# Quadflat-customized.net
KiCad netlist of a schematic drawn in EAGLE
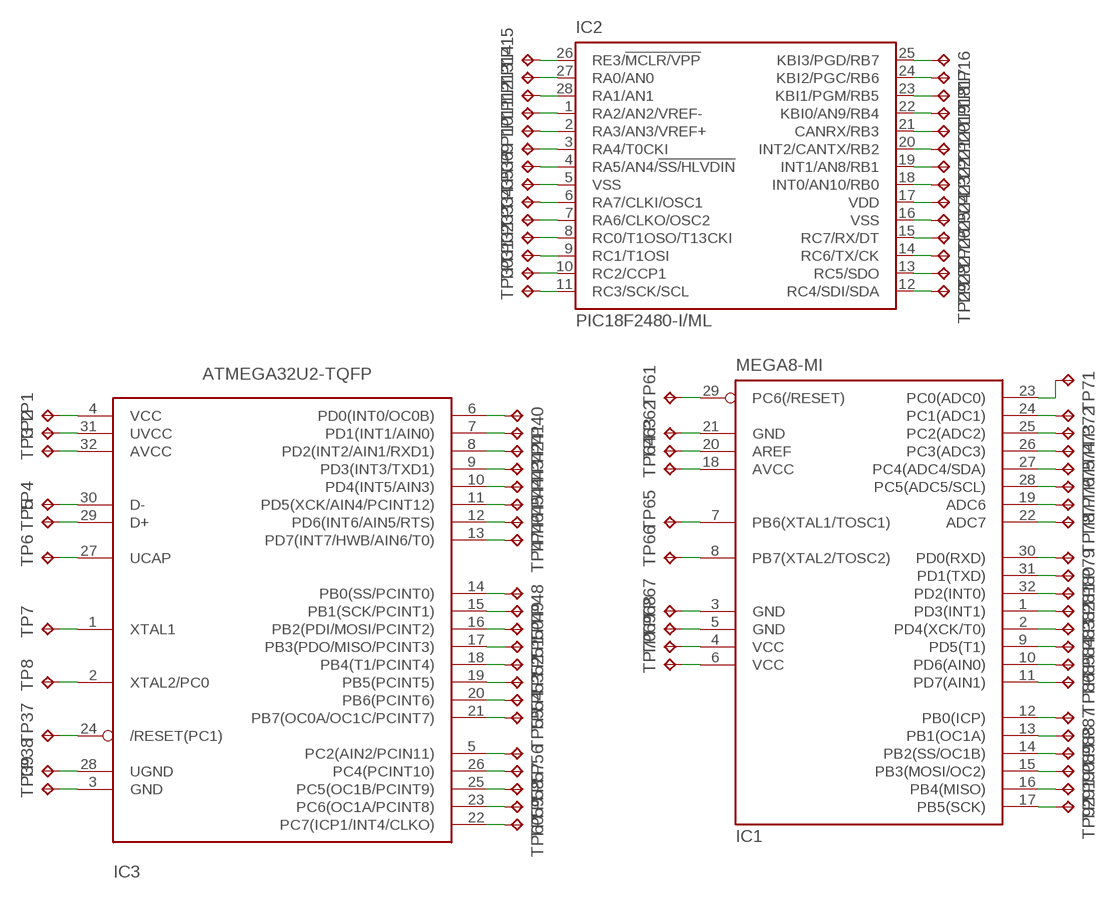
[diagram p0: schematic, sheet 2]

(export (version "E")
  (design (tool "Eeschema 10.0.6"))
  (components
    (comp (ref "IC1")
      (value "MEGA8-MI")
      (footprint "eagle-import:MLF32")
      (fields (field (name "MPN") "ATMEGA88PA-MU"))
      (libsource (lib "eagle-import") (part "MEGA8-MI"))
    )
    (comp (ref "IC2")
      (value "PIC18F2480-I/ML")
      (footprint "eagle-import:QFN28-ML_6X6MM")
      (fields (field (name "MF") "MICROCHIP"))
      (libsource (lib "eagle-import") (part "PIC18F280-I/ML4"))
    )
    (comp (ref "IC3")
      (value "ATMEGA32U2-TQFP")
      (footprint "eagle-import:TQFP32-08")
      (libsource (lib "eagle-import") (part "ATMEGA32U2-TQFP"))
    )
    (comp (ref "TP1")
      (value "TPPAD1-13Y")
      (footprint "eagle-import:P1-13Y")
      (libsource (lib "eagle-import") (part "TPPAD1-13Y"))
    )
    (comp (ref "TP2")
      (value "TPPAD1-13Y")
      (footprint "eagle-import:P1-13Y")
      (libsource (lib "eagle-import") (part "TPPAD1-13Y"))
    )
    (comp (ref "TP3")
      (value "TPPAD1-13Y")
      (footprint "eagle-import:P1-13Y")
      (libsource (lib "eagle-import") (part "TPPAD1-13Y"))
    )
    (comp (ref "TP4")
      (value "TPPAD1-13Y")
      (footprint "eagle-import:P1-13Y")
      (libsource (lib "eagle-import") (part "TPPAD1-13Y"))
    )
    (comp (ref "TP5")
      (value "TPPAD1-13Y")
      (footprint "eagle-import:P1-13Y")
      (libsource (lib "eagle-import") (part "TPPAD1-13Y"))
    )
    (comp (ref "TP6")
      (value "TPPAD1-13Y")
      (footprint "eagle-import:P1-13Y")
      (libsource (lib "eagle-import") (part "TPPAD1-13Y"))
    )
    (comp (ref "TP7")
      (value "TPPAD1-13Y")
      (footprint "eagle-import:P1-13Y")
      (libsource (lib "eagle-import") (part "TPPAD1-13Y"))
    )
    (comp (ref "TP8")
      (value "TPPAD1-13Y")
      (footprint "eagle-import:P1-13Y")
      (libsource (lib "eagle-import") (part "TPPAD1-13Y"))
    )
    (comp (ref "TP9")
      (value "TPPAD1-13Y")
      (footprint "eagle-import:P1-13Y")
      (libsource (lib "eagle-import") (part "TPPAD1-13Y"))
    )
    (comp (ref "TP10")
      (value "TPPAD1-13Y")
      (footprint "eagle-import:P1-13Y")
      (libsource (lib "eagle-import") (part "TPPAD1-13Y"))
    )
    (comp (ref "TP11")
      (value "TPPAD1-13Y")
      (footprint "eagle-import:P1-13Y")
      (libsource (lib "eagle-import") (part "TPPAD1-13Y"))
    )
    (comp (ref "TP12")
      (value "TPPAD1-13Y")
      (footprint "eagle-import:P1-13Y")
      (libsource (lib "eagle-import") (part "TPPAD1-13Y"))
    )
    (comp (ref "TP13")
      (value "TPPAD1-13Y")
      (footprint "eagle-import:P1-13Y")
      (libsource (lib "eagle-import") (part "TPPAD1-13Y"))
    )
    (comp (ref "TP14")
      (value "TPPAD1-13Y")
      (footprint "eagle-import:P1-13Y")
      (libsource (lib "eagle-import") (part "TPPAD1-13Y"))
    )
    (comp (ref "TP15")
      (value "TPPAD1-13Y")
      (footprint "eagle-import:P1-13Y")
      (libsource (lib "eagle-import") (part "TPPAD1-13Y"))
    )
    (comp (ref "TP16")
      (value "TPPAD1-13Y")
      (footprint "eagle-import:P1-13Y")
      (libsource (lib "eagle-import") (part "TPPAD1-13Y"))
    )
    (comp (ref "TP17")
      (value "TPPAD1-13Y")
      (footprint "eagle-import:P1-13Y")
      (libsource (lib "eagle-import") (part "TPPAD1-13Y"))
    )
    (comp (ref "TP18")
      (value "TPPAD1-13Y")
      (footprint "eagle-import:P1-13Y")
      (libsource (lib "eagle-import") (part "TPPAD1-13Y"))
    )
    (comp (ref "TP19")
      (value "TPPAD1-13Y")
      (footprint "eagle-import:P1-13Y")
      (libsource (lib "eagle-import") (part "TPPAD1-13Y"))
    )
    (comp (ref "TP20")
      (value "TPPAD1-13Y")
      (footprint "eagle-import:P1-13Y")
      (libsource (lib "eagle-import") (part "TPPAD1-13Y"))
    )
    (comp (ref "TP21")
      (value "TPPAD1-13Y")
      (footprint "eagle-import:P1-13Y")
      (libsource (lib "eagle-import") (part "TPPAD1-13Y"))
    )
    (comp (ref "TP22")
      (value "TPPAD1-13Y")
      (footprint "eagle-import:P1-13Y")
      (libsource (lib "eagle-import") (part "TPPAD1-13Y"))
    )
    (comp (ref "TP23")
      (value "TPPAD1-13Y")
      (footprint "eagle-import:P1-13Y")
      (libsource (lib "eagle-import") (part "TPPAD1-13Y"))
    )
    (comp (ref "TP24")
      (value "TPPAD1-13Y")
      (footprint "eagle-import:P1-13Y")
      (libsource (lib "eagle-import") (part "TPPAD1-13Y"))
    )
    (comp (ref "TP25")
      (value "TPPAD1-13Y")
      (footprint "eagle-import:P1-13Y")
      (libsource (lib "eagle-import") (part "TPPAD1-13Y"))
    )
    (comp (ref "TP26")
      (value "TPPAD1-13Y")
      (footprint "eagle-import:P1-13Y")
      (libsource (lib "eagle-import") (part "TPPAD1-13Y"))
    )
    (comp (ref "TP27")
      (value "TPPAD1-13Y")
      (footprint "eagle-import:P1-13Y")
      (libsource (lib "eagle-import") (part "TPPAD1-13Y"))
    )
    (comp (ref "TP28")
      (value "TPPAD1-13Y")
      (footprint "eagle-import:P1-13Y")
      (libsource (lib "eagle-import") (part "TPPAD1-13Y"))
    )
    (comp (ref "TP29")
      (value "TPPAD1-13Y")
      (footprint "eagle-import:P1-13Y")
      (libsource (lib "eagle-import") (part "TPPAD1-13Y"))
    )
    (comp (ref "TP30")
      (value "TPPAD1-13Y")
      (footprint "eagle-import:P1-13Y")
      (libsource (lib "eagle-import") (part "TPPAD1-13Y"))
    )
    (comp (ref "TP31")
      (value "TPPAD1-13Y")
      (footprint "eagle-import:P1-13Y")
      (libsource (lib "eagle-import") (part "TPPAD1-13Y"))
    )
    (comp (ref "TP32")
      (value "TPPAD1-13Y")
      (footprint "eagle-import:P1-13Y")
      (libsource (lib "eagle-import") (part "TPPAD1-13Y"))
    )
    (comp (ref "TP33")
      (value "TPPAD1-13Y")
      (footprint "eagle-import:P1-13Y")
      (libsource (lib "eagle-import") (part "TPPAD1-13Y"))
    )
    (comp (ref "TP34")
      (value "TPPAD1-13Y")
      (footprint "eagle-import:P1-13Y")
      (libsource (lib "eagle-import") (part "TPPAD1-13Y"))
    )
    (comp (ref "TP35")
      (value "TPPAD1-13Y")
      (footprint "eagle-import:P1-13Y")
      (libsource (lib "eagle-import") (part "TPPAD1-13Y"))
    )
    (comp (ref "TP36")
      (value "TPPAD1-13Y")
      (footprint "eagle-import:P1-13Y")
      (libsource (lib "eagle-import") (part "TPPAD1-13Y"))
    )
    (comp (ref "TP37")
      (value "TPPAD1-13Y")
      (footprint "eagle-import:P1-13Y")
      (libsource (lib "eagle-import") (part "TPPAD1-13Y"))
    )
    (comp (ref "TP38")
      (value "TPPAD1-13Y")
      (footprint "eagle-import:P1-13Y")
      (libsource (lib "eagle-import") (part "TPPAD1-13Y"))
    )
    (comp (ref "TP39")
      (value "TPPAD1-13Y")
      (footprint "eagle-import:P1-13Y")
      (libsource (lib "eagle-import") (part "TPPAD1-13Y"))
    )
    (comp (ref "TP40")
      (value "TPPAD1-13Y")
      (footprint "eagle-import:P1-13Y")
      (libsource (lib "eagle-import") (part "TPPAD1-13Y"))
    )
    (comp (ref "TP41")
      (value "TPPAD1-13Y")
      (footprint "eagle-import:P1-13Y")
      (libsource (lib "eagle-import") (part "TPPAD1-13Y"))
    )
    (comp (ref "TP42")
      (value "TPPAD1-13Y")
      (footprint "eagle-import:P1-13Y")
      (libsource (lib "eagle-import") (part "TPPAD1-13Y"))
    )
    (comp (ref "TP43")
      (value "TPPAD1-13Y")
      (footprint "eagle-import:P1-13Y")
      (libsource (lib "eagle-import") (part "TPPAD1-13Y"))
    )
    (comp (ref "TP44")
      (value "TPPAD1-13Y")
      (footprint "eagle-import:P1-13Y")
      (libsource (lib "eagle-import") (part "TPPAD1-13Y"))
    )
    (comp (ref "TP45")
      (value "TPPAD1-13Y")
      (footprint "eagle-import:P1-13Y")
      (libsource (lib "eagle-import") (part "TPPAD1-13Y"))
    )
    (comp (ref "TP46")
      (value "TPPAD1-13Y")
      (footprint "eagle-import:P1-13Y")
      (libsource (lib "eagle-import") (part "TPPAD1-13Y"))
    )
    (comp (ref "TP47")
      (value "TPPAD1-13Y")
      (footprint "eagle-import:P1-13Y")
      (libsource (lib "eagle-import") (part "TPPAD1-13Y"))
    )
    (comp (ref "TP48")
      (value "TPPAD1-13Y")
      (footprint "eagle-import:P1-13Y")
      (libsource (lib "eagle-import") (part "TPPAD1-13Y"))
    )
    (comp (ref "TP49")
      (value "TPPAD1-13Y")
      (footprint "eagle-import:P1-13Y")
      (libsource (lib "eagle-import") (part "TPPAD1-13Y"))
    )
    (comp (ref "TP50")
      (value "TPPAD1-13Y")
      (footprint "eagle-import:P1-13Y")
      (libsource (lib "eagle-import") (part "TPPAD1-13Y"))
    )
    (comp (ref "TP51")
      (value "TPPAD1-13Y")
      (footprint "eagle-import:P1-13Y")
      (libsource (lib "eagle-import") (part "TPPAD1-13Y"))
    )
    (comp (ref "TP52")
      (value "TPPAD1-13Y")
      (footprint "eagle-import:P1-13Y")
      (libsource (lib "eagle-import") (part "TPPAD1-13Y"))
    )
    (comp (ref "TP53")
      (value "TPPAD1-13Y")
      (footprint "eagle-import:P1-13Y")
      (libsource (lib "eagle-import") (part "TPPAD1-13Y"))
    )
    (comp (ref "TP54")
      (value "TPPAD1-13Y")
      (footprint "eagle-import:P1-13Y")
      (libsource (lib "eagle-import") (part "TPPAD1-13Y"))
    )
    (comp (ref "TP55")
      (value "TPPAD1-13Y")
      (footprint "eagle-import:P1-13Y")
      (libsource (lib "eagle-import") (part "TPPAD1-13Y"))
    )
    (comp (ref "TP56")
      (value "TPPAD1-13Y")
      (footprint "eagle-import:P1-13Y")
      (libsource (lib "eagle-import") (part "TPPAD1-13Y"))
    )
    (comp (ref "TP57")
      (value "TPPAD1-13Y")
      (footprint "eagle-import:P1-13Y")
      (libsource (lib "eagle-import") (part "TPPAD1-13Y"))
    )
    (comp (ref "TP58")
      (value "TPPAD1-13Y")
      (footprint "eagle-import:P1-13Y")
      (libsource (lib "eagle-import") (part "TPPAD1-13Y"))
    )
    (comp (ref "TP59")
      (value "TPPAD1-13Y")
      (footprint "eagle-import:P1-13Y")
      (libsource (lib "eagle-import") (part "TPPAD1-13Y"))
    )
    (comp (ref "TP60")
      (value "TPPAD1-13Y")
      (footprint "eagle-import:P1-13Y")
      (libsource (lib "eagle-import") (part "TPPAD1-13Y"))
    )
    (comp (ref "TP61")
      (value "TPPAD1-13Y")
      (footprint "eagle-import:P1-13Y")
      (libsource (lib "eagle-import") (part "TPPAD1-13Y"))
    )
    (comp (ref "TP62")
      (value "TPPAD1-13Y")
      (footprint "eagle-import:P1-13Y")
      (libsource (lib "eagle-import") (part "TPPAD1-13Y"))
    )
    (comp (ref "TP63")
      (value "TPPAD1-13Y")
      (footprint "eagle-import:P1-13Y")
      (libsource (lib "eagle-import") (part "TPPAD1-13Y"))
    )
    (comp (ref "TP64")
      (value "TPPAD1-13Y")
      (footprint "eagle-import:P1-13Y")
      (libsource (lib "eagle-import") (part "TPPAD1-13Y"))
    )
    (comp (ref "TP65")
      (value "TPPAD1-13Y")
      (footprint "eagle-import:P1-13Y")
      (libsource (lib "eagle-import") (part "TPPAD1-13Y"))
    )
    (comp (ref "TP66")
      (value "TPPAD1-13Y")
      (footprint "eagle-import:P1-13Y")
      (libsource (lib "eagle-import") (part "TPPAD1-13Y"))
    )
    (comp (ref "TP67")
      (value "TPPAD1-13Y")
      (footprint "eagle-import:P1-13Y")
      (libsource (lib "eagle-import") (part "TPPAD1-13Y"))
    )
    (comp (ref "TP68")
      (value "TPPAD1-13Y")
      (footprint "eagle-import:P1-13Y")
      (libsource (lib "eagle-import") (part "TPPAD1-13Y"))
    )
    (comp (ref "TP69")
      (value "TPPAD1-13Y")
      (footprint "eagle-import:P1-13Y")
      (libsource (lib "eagle-import") (part "TPPAD1-13Y"))
    )
    (comp (ref "TP70")
      (value "TPPAD1-13Y")
      (footprint "eagle-import:P1-13Y")
      (libsource (lib "eagle-import") (part "TPPAD1-13Y"))
    )
    (comp (ref "TP71")
      (value "TPPAD1-13Y")
      (footprint "eagle-import:P1-13Y")
      (libsource (lib "eagle-import") (part "TPPAD1-13Y"))
    )
    (comp (ref "TP72")
      (value "TPPAD1-13Y")
      (footprint "eagle-import:P1-13Y")
      (libsource (lib "eagle-import") (part "TPPAD1-13Y"))
    )
    (comp (ref "TP73")
      (value "TPPAD1-13Y")
      (footprint "eagle-import:P1-13Y")
      (libsource (lib "eagle-import") (part "TPPAD1-13Y"))
    )
    (comp (ref "TP74")
      (value "TPPAD1-13Y")
      (footprint "eagle-import:P1-13Y")
      (libsource (lib "eagle-import") (part "TPPAD1-13Y"))
    )
    (comp (ref "TP75")
      (value "TPPAD1-13Y")
      (footprint "eagle-import:P1-13Y")
      (libsource (lib "eagle-import") (part "TPPAD1-13Y"))
    )
    (comp (ref "TP76")
      (value "TPPAD1-13Y")
      (footprint "eagle-import:P1-13Y")
      (libsource (lib "eagle-import") (part "TPPAD1-13Y"))
    )
    (comp (ref "TP77")
      (value "TPPAD1-13Y")
      (footprint "eagle-import:P1-13Y")
      (libsource (lib "eagle-import") (part "TPPAD1-13Y"))
    )
    (comp (ref "TP78")
      (value "TPPAD1-13Y")
      (footprint "eagle-import:P1-13Y")
      (libsource (lib "eagle-import") (part "TPPAD1-13Y"))
    )
    (comp (ref "TP79")
      (value "TPPAD1-13Y")
      (footprint "eagle-import:P1-13Y")
      (libsource (lib "eagle-import") (part "TPPAD1-13Y"))
    )
    (comp (ref "TP80")
      (value "TPPAD1-13Y")
      (footprint "eagle-import:P1-13Y")
      (libsource (lib "eagle-import") (part "TPPAD1-13Y"))
    )
    (comp (ref "TP81")
      (value "TPPAD1-13Y")
      (footprint "eagle-import:P1-13Y")
      (libsource (lib "eagle-import") (part "TPPAD1-13Y"))
    )
    (comp (ref "TP82")
      (value "TPPAD1-13Y")
      (footprint "eagle-import:P1-13Y")
      (libsource (lib "eagle-import") (part "TPPAD1-13Y"))
    )
    (comp (ref "TP83")
      (value "TPPAD1-13Y")
      (footprint "eagle-import:P1-13Y")
      (libsource (lib "eagle-import") (part "TPPAD1-13Y"))
    )
    (comp (ref "TP84")
      (value "TPPAD1-13Y")
      (footprint "eagle-import:P1-13Y")
      (libsource (lib "eagle-import") (part "TPPAD1-13Y"))
    )
    (comp (ref "TP85")
      (value "TPPAD1-13Y")
      (footprint "eagle-import:P1-13Y")
      (libsource (lib "eagle-import") (part "TPPAD1-13Y"))
    )
    (comp (ref "TP86")
      (value "TPPAD1-13Y")
      (footprint "eagle-import:P1-13Y")
      (libsource (lib "eagle-import") (part "TPPAD1-13Y"))
    )
    (comp (ref "TP87")
      (value "TPPAD1-13Y")
      (footprint "eagle-import:P1-13Y")
      (libsource (lib "eagle-import") (part "TPPAD1-13Y"))
    )
    (comp (ref "TP88")
      (value "TPPAD1-13Y")
      (footprint "eagle-import:P1-13Y")
      (libsource (lib "eagle-import") (part "TPPAD1-13Y"))
    )
    (comp (ref "TP89")
      (value "TPPAD1-13Y")
      (footprint "eagle-import:P1-13Y")
      (libsource (lib "eagle-import") (part "TPPAD1-13Y"))
    )
    (comp (ref "TP90")
      (value "TPPAD1-13Y")
      (footprint "eagle-import:P1-13Y")
      (libsource (lib "eagle-import") (part "TPPAD1-13Y"))
    )
    (comp (ref "TP91")
      (value "TPPAD1-13Y")
      (footprint "eagle-import:P1-13Y")
      (libsource (lib "eagle-import") (part "TPPAD1-13Y"))
    )
    (comp (ref "TP92")
      (value "TPPAD1-13Y")
      (footprint "eagle-import:P1-13Y")
      (libsource (lib "eagle-import") (part "TPPAD1-13Y"))
    )
  )
  (nets
    (net (code "1") (name "Net-(IC1-ADC6)") (class "Default")
      (node (ref "IC1") (pin "19") (pinfunction "ADC6_19") (pintype "bidirectional"))
      (node (ref "TP77") (pin "TP") (pinfunction "TP_TP") (pintype "input"))
    )
    (net (code "2") (name "Net-(IC1-ADC7)") (class "Default")
      (node (ref "IC1") (pin "22") (pinfunction "ADC7_22") (pintype "bidirectional"))
      (node (ref "TP78") (pin "TP") (pinfunction "TP_TP") (pintype "input"))
    )
    (net (code "3") (name "Net-(IC1-AREF)") (class "Default")
      (node (ref "IC1") (pin "20") (pinfunction "AREF_20") (pintype "passive"))
      (node (ref "TP63") (pin "TP") (pinfunction "TP_TP") (pintype "input"))
    )
    (net (code "4") (name "Net-(IC1-AVCC)") (class "Default")
      (node (ref "IC1") (pin "18") (pinfunction "AVCC_18") (pintype "power_in"))
      (node (ref "TP64") (pin "TP") (pinfunction "TP_TP") (pintype "input"))
    )
    (net (code "5") (name "Net-(IC1-GND-Pad3)") (class "Default")
      (node (ref "IC1") (pin "3") (pinfunction "GND_3") (pintype "power_in"))
      (node (ref "TP67") (pin "TP") (pinfunction "TP_TP") (pintype "input"))
    )
    (net (code "6") (name "Net-(IC1-GND-Pad5)") (class "Default")
      (node (ref "IC1") (pin "5") (pinfunction "GND_5") (pintype "power_in"))
      (node (ref "TP68") (pin "TP") (pinfunction "TP_TP") (pintype "input"))
    )
    (net (code "7") (name "Net-(IC1-GND-Pad21)") (class "Default")
      (node (ref "IC1") (pin "21") (pinfunction "GND_21") (pintype "power_in"))
      (node (ref "TP62") (pin "TP") (pinfunction "TP_TP") (pintype "input"))
    )
    (net (code "8") (name "Net-(IC1-PB0(ICP))") (class "Default")
      (node (ref "IC1") (pin "12") (pinfunction "PB0(ICP)_12") (pintype "bidirectional"))
      (node (ref "TP87") (pin "TP") (pinfunction "TP_TP") (pintype "input"))
    )
    (net (code "9") (name "Net-(IC1-PB1(OC1A))") (class "Default")
      (node (ref "IC1") (pin "13") (pinfunction "PB1(OC1A)_13") (pintype "bidirectional"))
      (node (ref "TP88") (pin "TP") (pinfunction "TP_TP") (pintype "input"))
    )
    (net (code "10") (name "Net-(IC1-PB2(SS{slash}OC1B))") (class "Default")
      (node (ref "IC1") (pin "14") (pinfunction "PB2(SS/OC1B)_14") (pintype "bidirectional"))
      (node (ref "TP89") (pin "TP") (pinfunction "TP_TP") (pintype "input"))
    )
    (net (code "11") (name "Net-(IC1-PB3(MOSI{slash}OC2))") (class "Default")
      (node (ref "IC1") (pin "15") (pinfunction "PB3(MOSI/OC2)_15") (pintype "bidirectional"))
      (node (ref "TP90") (pin "TP") (pinfunction "TP_TP") (pintype "input"))
    )
    (net (code "12") (name "Net-(IC1-PB4(MISO))") (class "Default")
      (node (ref "IC1") (pin "16") (pinfunction "PB4(MISO)_16") (pintype "bidirectional"))
      (node (ref "TP91") (pin "TP") (pinfunction "TP_TP") (pintype "input"))
    )
    (net (code "13") (name "Net-(IC1-PB5(SCK))") (class "Default")
      (node (ref "IC1") (pin "17") (pinfunction "PB5(SCK)_17") (pintype "bidirectional"))
      (node (ref "TP92") (pin "TP") (pinfunction "TP_TP") (pintype "input"))
    )
    (net (code "14") (name "Net-(IC1-PB6(XTAL1{slash}TOSC1))") (class "Default")
      (node (ref "IC1") (pin "7") (pinfunction "PB6(XTAL1/TOSC1)_7") (pintype "bidirectional"))
      (node (ref "TP65") (pin "TP") (pinfunction "TP_TP") (pintype "input"))
    )
    (net (code "15") (name "Net-(IC1-PB7(XTAL2{slash}TOSC2))") (class "Default")
      (node (ref "IC1") (pin "8") (pinfunction "PB7(XTAL2/TOSC2)_8") (pintype "bidirectional"))
      (node (ref "TP66") (pin "TP") (pinfunction "TP_TP") (pintype "input"))
    )
    (net (code "16") (name "Net-(IC1-PC0(ADC0))") (class "Default")
      (node (ref "IC1") (pin "23") (pinfunction "PC0(ADC0)_23") (pintype "bidirectional"))
      (node (ref "TP71") (pin "TP") (pinfunction "TP_TP") (pintype "input"))
    )
    (net (code "17") (name "Net-(IC1-PC1(ADC1))") (class "Default")
      (node (ref "IC1") (pin "24") (pinfunction "PC1(ADC1)_24") (pintype "bidirectional"))
      (node (ref "TP72") (pin "TP") (pinfunction "TP_TP") (pintype "input"))
    )
    (net (code "18") (name "Net-(IC1-PC2(ADC2))") (class "Default")
      (node (ref "IC1") (pin "25") (pinfunction "PC2(ADC2)_25") (pintype "bidirectional"))
      (node (ref "TP73") (pin "TP") (pinfunction "TP_TP") (pintype "input"))
    )
    (net (code "19") (name "Net-(IC1-PC3(ADC3))") (class "Default")
      (node (ref "IC1") (pin "26") (pinfunction "PC3(ADC3)_26") (pintype "bidirectional"))
      (node (ref "TP74") (pin "TP") (pinfunction "TP_TP") (pintype "input"))
    )
    (net (code "20") (name "Net-(IC1-PC4(ADC4{slash}SDA))") (class "Default")
      (node (ref "IC1") (pin "27") (pinfunction "PC4(ADC4/SDA)_27") (pintype "bidirectional"))
      (node (ref "TP75") (pin "TP") (pinfunction "TP_TP") (pintype "input"))
    )
    (net (code "21") (name "Net-(IC1-PC5(ADC5{slash}SCL))") (class "Default")
      (node (ref "IC1") (pin "28") (pinfunction "PC5(ADC5/SCL)_28") (pintype "bidirectional"))
      (node (ref "TP76") (pin "TP") (pinfunction "TP_TP") (pintype "input"))
    )
    (net (code "22") (name "Net-(IC1-PC6({slash}RESET))") (class "Default")
      (node (ref "IC1") (pin "29") (pinfunction "PC6(/RESET)_29") (pintype "bidirectional"))
      (node (ref "TP61") (pin "TP") (pinfunction "TP_TP") (pintype "input"))
    )
    (net (code "23") (name "Net-(IC1-PD0(RXD))") (class "Default")
      (node (ref "IC1") (pin "30") (pinfunction "PD0(RXD)_30") (pintype "bidirectional"))
      (node (ref "TP79") (pin "TP") (pinfunction "TP_TP") (pintype "input"))
    )
    (net (code "24") (name "Net-(IC1-PD1(TXD))") (class "Default")
      (node (ref "IC1") (pin "31") (pinfunction "PD1(TXD)_31") (pintype "bidirectional"))
      (node (ref "TP80") (pin "TP") (pinfunction "TP_TP") (pintype "input"))
    )
    (net (code "25") (name "Net-(IC1-PD2(INT0))") (class "Default")
      (node (ref "IC1") (pin "32") (pinfunction "PD2(INT0)_32") (pintype "bidirectional"))
      (node (ref "TP81") (pin "TP") (pinfunction "TP_TP") (pintype "input"))
    )
    (net (code "26") (name "Net-(IC1-PD3(INT1))") (class "Default")
      (node (ref "IC1") (pin "1") (pinfunction "PD3(INT1)_1") (pintype "bidirectional"))
      (node (ref "TP82") (pin "TP") (pinfunction "TP_TP") (pintype "input"))
    )
    (net (code "27") (name "Net-(IC1-PD4(XCK{slash}T0))") (class "Default")
      (node (ref "IC1") (pin "2") (pinfunction "PD4(XCK/T0)_2") (pintype "bidirectional"))
      (node (ref "TP83") (pin "TP") (pinfunction "TP_TP") (pintype "input"))
    )
    (net (code "28") (name "Net-(IC1-PD5(T1))") (class "Default")
      (node (ref "IC1") (pin "9") (pinfunction "PD5(T1)_9") (pintype "bidirectional"))
      (node (ref "TP84") (pin "TP") (pinfunction "TP_TP") (pintype "input"))
    )
    (net (code "29") (name "Net-(IC1-PD6(AIN0))") (class "Default")
      (node (ref "IC1") (pin "10") (pinfunction "PD6(AIN0)_10") (pintype "bidirectional"))
      (node (ref "TP85") (pin "TP") (pinfunction "TP_TP") (pintype "input"))
    )
    (net (code "30") (name "Net-(IC1-PD7(AIN1))") (class "Default")
      (node (ref "IC1") (pin "11") (pinfunction "PD7(AIN1)_11") (pintype "bidirectional"))
      (node (ref "TP86") (pin "TP") (pinfunction "TP_TP") (pintype "input"))
    )
    (net (code "31") (name "Net-(IC1-VCC-Pad4)") (class "Default")
      (node (ref "IC1") (pin "4") (pinfunction "VCC_4") (pintype "power_in"))
      (node (ref "TP69") (pin "TP") (pinfunction "TP_TP") (pintype "input"))
    )
    (net (code "32") (name "Net-(IC1-VCC-Pad6)") (class "Default")
      (node (ref "IC1") (pin "6") (pinfunction "VCC_6") (pintype "power_in"))
      (node (ref "TP70") (pin "TP") (pinfunction "TP_TP") (pintype "input"))
    )
    (net (code "33") (name "Net-(IC2-CANRX{slash}RB3)") (class "Default")
      (node (ref "IC2") (pin "21") (pinfunction "CANRX/RB3_21") (pintype "bidirectional"))
      (node (ref "TP20") (pin "TP") (pinfunction "TP_TP") (pintype "input"))
    )
    (net (code "34") (name "Net-(IC2-INT0{slash}AN10{slash}RB0)") (class "Default")
      (node (ref "IC2") (pin "18") (pinfunction "INT0/AN10/RB0_18") (pintype "bidirectional"))
      (node (ref "TP23") (pin "TP") (pinfunction "TP_TP") (pintype "input"))
    )
    (net (code "35") (name "Net-(IC2-INT1{slash}AN8{slash}RB1)") (class "Default")
      (node (ref "IC2") (pin "19") (pinfunction "INT1/AN8/RB1_19") (pintype "bidirectional"))
      (node (ref "TP22") (pin "TP") (pinfunction "TP_TP") (pintype "input"))
    )
    (net (code "36") (name "Net-(IC2-INT2{slash}CANTX{slash}RB2)") (class "Default")
      (node (ref "IC2") (pin "20") (pinfunction "INT2/CANTX/RB2_20") (pintype "bidirectional"))
      (node (ref "TP21") (pin "TP") (pinfunction "TP_TP") (pintype "input"))
    )
    (net (code "37") (name "Net-(IC2-KBI0{slash}AN9{slash}RB4)") (class "Default")
      (node (ref "IC2") (pin "22") (pinfunction "KBI0/AN9/RB4_22") (pintype "bidirectional"))
      (node (ref "TP19") (pin "TP") (pinfunction "TP_TP") (pintype "input"))
    )
    (net (code "38") (name "Net-(IC2-KBI1{slash}PGM{slash}RB5)") (class "Default")
      (node (ref "IC2") (pin "23") (pinfunction "KBI1/PGM/RB5_23") (pintype "bidirectional"))
      (node (ref "TP18") (pin "TP") (pinfunction "TP_TP") (pintype "input"))
    )
    (net (code "39") (name "Net-(IC2-KBI2{slash}PGC{slash}RB6)") (class "Default")
      (node (ref "IC2") (pin "24") (pinfunction "KBI2/PGC/RB6_24") (pintype "bidirectional"))
      (node (ref "TP17") (pin "TP") (pinfunction "TP_TP") (pintype "input"))
    )
    (net (code "40") (name "Net-(IC2-KBI3{slash}PGD{slash}RB7)") (class "Default")
      (node (ref "IC2") (pin "25") (pinfunction "KBI3/PGD/RB7_25") (pintype "bidirectional"))
      (node (ref "TP16") (pin "TP") (pinfunction "TP_TP") (pintype "input"))
    )
    (net (code "41") (name "Net-(IC2-RA0{slash}AN0)") (class "Default")
      (node (ref "IC2") (pin "27") (pinfunction "RA0/AN0_27") (pintype "bidirectional"))
      (node (ref "TP14") (pin "TP") (pinfunction "TP_TP") (pintype "input"))
    )
    (net (code "42") (name "Net-(IC2-RA1{slash}AN1)") (class "Default")
      (node (ref "IC2") (pin "28") (pinfunction "RA1/AN1_28") (pintype "bidirectional"))
      (node (ref "TP13") (pin "TP") (pinfunction "TP_TP") (pintype "input"))
    )
    (net (code "43") (name "Net-(IC2-RA2{slash}AN2{slash}VREF-)") (class "Default")
      (node (ref "IC2") (pin "1") (pinfunction "RA2/AN2/VREF-_1") (pintype "bidirectional"))
      (node (ref "TP12") (pin "TP") (pinfunction "TP_TP") (pintype "input"))
    )
    (net (code "44") (name "Net-(IC2-RA3{slash}AN3{slash}VREF+)") (class "Default")
      (node (ref "IC2") (pin "2") (pinfunction "RA3/AN3/VREF+_2") (pintype "bidirectional"))
      (node (ref "TP11") (pin "TP") (pinfunction "TP_TP") (pintype "input"))
    )
    (net (code "45") (name "Net-(IC2-RA4{slash}T0CKI)") (class "Default")
      (node (ref "IC2") (pin "3") (pinfunction "RA4/T0CKI_3") (pintype "bidirectional"))
      (node (ref "TP10") (pin "TP") (pinfunction "TP_TP") (pintype "input"))
    )
    (net (code "46") (name "Net-(IC2-RA5{slash}AN4{slash}~{SS{slash}HLVDIN})") (class "Default")
      (node (ref "IC2") (pin "4") (pinfunction "RA5/AN4/~{SS/HLVDIN}_4") (pintype "bidirectional"))
      (node (ref "TP9") (pin "TP") (pinfunction "TP_TP") (pintype "input"))
    )
    (net (code "47") (name "Net-(IC2-RA6{slash}CLKO{slash}OSC2)") (class "Default")
      (node (ref "IC2") (pin "7") (pinfunction "RA6/CLKO/OSC2_7") (pintype "output"))
      (node (ref "TP34") (pin "TP") (pinfunction "TP_TP") (pintype "input"))
    )
    (net (code "48") (name "Net-(IC2-RA7{slash}CLKI{slash}OSC1)") (class "Default")
      (node (ref "IC2") (pin "6") (pinfunction "RA7/CLKI/OSC1_6") (pintype "input"))
      (node (ref "TP35") (pin "TP") (pinfunction "TP_TP") (pintype "input"))
    )
    (net (code "49") (name "Net-(IC2-RC0{slash}T1OSO{slash}T13CKI)") (class "Default")
      (node (ref "IC2") (pin "8") (pinfunction "RC0/T1OSO/T13CKI_8") (pintype "bidirectional"))
      (node (ref "TP33") (pin "TP") (pinfunction "TP_TP") (pintype "input"))
    )
    (net (code "50") (name "Net-(IC2-RC1{slash}T1OSI)") (class "Default")
      (node (ref "IC2") (pin "9") (pinfunction "RC1/T1OSI_9") (pintype "bidirectional"))
      (node (ref "TP32") (pin "TP") (pinfunction "TP_TP") (pintype "input"))
    )
    (net (code "51") (name "Net-(IC2-RC2{slash}CCP1)") (class "Default")
      (node (ref "IC2") (pin "10") (pinfunction "RC2/CCP1_10") (pintype "bidirectional"))
      (node (ref "TP31") (pin "TP") (pinfunction "TP_TP") (pintype "input"))
    )
    (net (code "52") (name "Net-(IC2-RC3{slash}SCK{slash}SCL)") (class "Default")
      (node (ref "IC2") (pin "11") (pinfunction "RC3/SCK/SCL_11") (pintype "bidirectional"))
      (node (ref "TP30") (pin "TP") (pinfunction "TP_TP") (pintype "input"))
    )
    (net (code "53") (name "Net-(IC2-RC4{slash}SDI{slash}SDA)") (class "Default")
      (node (ref "IC2") (pin "12") (pinfunction "RC4/SDI/SDA_12") (pintype "bidirectional"))
      (node (ref "TP29") (pin "TP") (pinfunction "TP_TP") (pintype "input"))
    )
    (net (code "54") (name "Net-(IC2-RC5{slash}SDO)") (class "Default")
      (node (ref "IC2") (pin "13") (pinfunction "RC5/SDO_13") (pintype "bidirectional"))
      (node (ref "TP28") (pin "TP") (pinfunction "TP_TP") (pintype "input"))
    )
    (net (code "55") (name "Net-(IC2-RC6{slash}TX{slash}CK)") (class "Default")
      (node (ref "IC2") (pin "14") (pinfunction "RC6/TX/CK_14") (pintype "bidirectional"))
      (node (ref "TP27") (pin "TP") (pinfunction "TP_TP") (pintype "input"))
    )
    (net (code "56") (name "Net-(IC2-RC7{slash}RX{slash}DT)") (class "Default")
      (node (ref "IC2") (pin "15") (pinfunction "RC7/RX/DT_15") (pintype "bidirectional"))
      (node (ref "TP26") (pin "TP") (pinfunction "TP_TP") (pintype "input"))
    )
    (net (code "57") (name "Net-(IC2-RE3{slash}~{MCLR{slash}VPP})") (class "Default")
      (node (ref "IC2") (pin "26") (pinfunction "RE3/~{MCLR/VPP}_26") (pintype "input"))
      (node (ref "TP15") (pin "TP") (pinfunction "TP_TP") (pintype "input"))
    )
    (net (code "58") (name "Net-(IC2-VDD)") (class "Default")
      (node (ref "IC2") (pin "17") (pinfunction "VDD_17") (pintype "power_in"))
      (node (ref "TP24") (pin "TP") (pinfunction "TP_TP") (pintype "input"))
    )
    (net (code "59") (name "Net-(IC2-VSS-Pad5)") (class "Default")
      (node (ref "IC2") (pin "5") (pinfunction "VSS_5") (pintype "power_in"))
      (node (ref "TP36") (pin "TP") (pinfunction "TP_TP") (pintype "input"))
    )
    (net (code "60") (name "Net-(IC2-VSS-Pad16)") (class "Default")
      (node (ref "IC2") (pin "16") (pinfunction "VSS_16") (pintype "power_in"))
      (node (ref "TP25") (pin "TP") (pinfunction "TP_TP") (pintype "input"))
    )
    (net (code "61") (name "Net-(IC3-AVCC)") (class "Default")
      (node (ref "IC3") (pin "32") (pinfunction "AVCC_32") (pintype "bidirectional"))
      (node (ref "TP3") (pin "TP") (pinfunction "TP_TP") (pintype "input"))
    )
    (net (code "62") (name "Net-(IC3-D+)") (class "Default")
      (node (ref "IC3") (pin "29") (pinfunction "D+_29") (pintype "bidirectional"))
      (node (ref "TP5") (pin "TP") (pinfunction "TP_TP") (pintype "input"))
    )
    (net (code "63") (name "Net-(IC3-D-)") (class "Default")
      (node (ref "IC3") (pin "30") (pinfunction "D-_30") (pintype "bidirectional"))
      (node (ref "TP4") (pin "TP") (pinfunction "TP_TP") (pintype "input"))
    )
    (net (code "64") (name "Net-(IC3-GND)") (class "Default")
      (node (ref "IC3") (pin "3") (pinfunction "GND_3") (pintype "bidirectional"))
      (node (ref "TP39") (pin "TP") (pinfunction "TP_TP") (pintype "input"))
    )
    (net (code "65") (name "Net-(IC3-PB0(SS{slash}PCINT0))") (class "Default")
      (node (ref "IC3") (pin "14") (pinfunction "PB0(SS/PCINT0)_14") (pintype "bidirectional"))
      (node (ref "TP48") (pin "TP") (pinfunction "TP_TP") (pintype "input"))
    )
    (net (code "66") (name "Net-(IC3-PB1(SCK{slash}PCINT1))") (class "Default")
      (node (ref "IC3") (pin "15") (pinfunction "PB1(SCK/PCINT1)_15") (pintype "bidirectional"))
      (node (ref "TP49") (pin "TP") (pinfunction "TP_TP") (pintype "input"))
    )
    (net (code "67") (name "Net-(IC3-PB2(PDI{slash}MOSI{slash}PCINT2))") (class "Default")
      (node (ref "IC3") (pin "16") (pinfunction "PB2(PDI/MOSI/PCINT2)_16") (pintype "bidirectional"))
      (node (ref "TP50") (pin "TP") (pinfunction "TP_TP") (pintype "input"))
    )
    (net (code "68") (name "Net-(IC3-PB3(PDO{slash}MISO{slash}PCINT3))") (class "Default")
      (node (ref "IC3") (pin "17") (pinfunction "PB3(PDO/MISO/PCINT3)_17") (pintype "bidirectional"))
      (node (ref "TP51") (pin "TP") (pinfunction "TP_TP") (pintype "input"))
    )
    (net (code "69") (name "Net-(IC3-PB4(T1{slash}PCINT4))") (class "Default")
      (node (ref "IC3") (pin "18") (pinfunction "PB4(T1/PCINT4)_18") (pintype "bidirectional"))
      (node (ref "TP52") (pin "TP") (pinfunction "TP_TP") (pintype "input"))
    )
    (net (code "70") (name "Net-(IC3-PB5(PCINT5))") (class "Default")
      (node (ref "IC3") (pin "19") (pinfunction "PB5(PCINT5)_19") (pintype "bidirectional"))
      (node (ref "TP53") (pin "TP") (pinfunction "TP_TP") (pintype "input"))
    )
    (net (code "71") (name "Net-(IC3-PB6(PCINT6))") (class "Default")
      (node (ref "IC3") (pin "20") (pinfunction "PB6(PCINT6)_20") (pintype "bidirectional"))
      (node (ref "TP54") (pin "TP") (pinfunction "TP_TP") (pintype "input"))
    )
    (net (code "72") (name "Net-(IC3-PB7(OC0A{slash}OC1C{slash}PCINT7))") (class "Default")
      (node (ref "IC3") (pin "21") (pinfunction "PB7(OC0A/OC1C/PCINT7)_21") (pintype "bidirectional"))
      (node (ref "TP55") (pin "TP") (pinfunction "TP_TP") (pintype "input"))
    )
    (net (code "73") (name "Net-(IC3-PC2(AIN2{slash}PCIN11))") (class "Default")
      (node (ref "IC3") (pin "5") (pinfunction "PC2(AIN2/PCIN11)_5") (pintype "bidirectional"))
      (node (ref "TP56") (pin "TP") (pinfunction "TP_TP") (pintype "input"))
    )
    (net (code "74") (name "Net-(IC3-PC4(PCINT10))") (class "Default")
      (node (ref "IC3") (pin "26") (pinfunction "PC4(PCINT10)_26") (pintype "bidirectional"))
      (node (ref "TP57") (pin "TP") (pinfunction "TP_TP") (pintype "input"))
    )
    (net (code "75") (name "Net-(IC3-PC5(OC1B{slash}PCINT9))") (class "Default")
      (node (ref "IC3") (pin "25") (pinfunction "PC5(OC1B/PCINT9)_25") (pintype "bidirectional"))
      (node (ref "TP58") (pin "TP") (pinfunction "TP_TP") (pintype "input"))
    )
    (net (code "76") (name "Net-(IC3-PC6(OC1A{slash}PCINT8))") (class "Default")
      (node (ref "IC3") (pin "23") (pinfunction "PC6(OC1A/PCINT8)_23") (pintype "bidirectional"))
      (node (ref "TP59") (pin "TP") (pinfunction "TP_TP") (pintype "input"))
    )
    (net (code "77") (name "Net-(IC3-PC7(ICP1{slash}INT4{slash}CLKO))") (class "Default")
      (node (ref "IC3") (pin "22") (pinfunction "PC7(ICP1/INT4/CLKO)_22") (pintype "bidirectional"))
      (node (ref "TP60") (pin "TP") (pinfunction "TP_TP") (pintype "input"))
    )
    (net (code "78") (name "Net-(IC3-PD0(INT0{slash}OC0B))") (class "Default")
      (node (ref "IC3") (pin "6") (pinfunction "PD0(INT0/OC0B)_6") (pintype "bidirectional"))
      (node (ref "TP40") (pin "TP") (pinfunction "TP_TP") (pintype "input"))
    )
    (net (code "79") (name "Net-(IC3-PD1(INT1{slash}AIN0))") (class "Default")
      (node (ref "IC3") (pin "7") (pinfunction "PD1(INT1/AIN0)_7") (pintype "bidirectional"))
      (node (ref "TP41") (pin "TP") (pinfunction "TP_TP") (pintype "input"))
    )
    (net (code "80") (name "Net-(IC3-PD2(INT2{slash}AIN1{slash}RXD1))") (class "Default")
      (node (ref "IC3") (pin "8") (pinfunction "PD2(INT2/AIN1/RXD1)_8") (pintype "bidirectional"))
      (node (ref "TP42") (pin "TP") (pinfunction "TP_TP") (pintype "input"))
    )
    (net (code "81") (name "Net-(IC3-PD3(INT3{slash}TXD1))") (class "Default")
      (node (ref "IC3") (pin "9") (pinfunction "PD3(INT3/TXD1)_9") (pintype "bidirectional"))
      (node (ref "TP43") (pin "TP") (pinfunction "TP_TP") (pintype "input"))
    )
    (net (code "82") (name "Net-(IC3-PD4(INT5{slash}AIN3))") (class "Default")
      (node (ref "IC3") (pin "10") (pinfunction "PD4(INT5/AIN3)_10") (pintype "bidirectional"))
      (node (ref "TP44") (pin "TP") (pinfunction "TP_TP") (pintype "input"))
    )
    (net (code "83") (name "Net-(IC3-PD5(XCK{slash}AIN4{slash}PCINT12))") (class "Default")
      (node (ref "IC3") (pin "11") (pinfunction "PD5(XCK/AIN4/PCINT12)_11") (pintype "bidirectional"))
      (node (ref "TP45") (pin "TP") (pinfunction "TP_TP") (pintype "input"))
    )
    (net (code "84") (name "Net-(IC3-PD6(INT6{slash}AIN5{slash}RTS))") (class "Default")
      (node (ref "IC3") (pin "12") (pinfunction "PD6(INT6/AIN5/RTS)_12") (pintype "bidirectional"))
      (node (ref "TP46") (pin "TP") (pinfunction "TP_TP") (pintype "input"))
    )
    (net (code "85") (name "Net-(IC3-PD7(INT7{slash}HWB{slash}AIN6{slash}T0))") (class "Default")
      (node (ref "IC3") (pin "13") (pinfunction "PD7(INT7/HWB/AIN6/T0)_13") (pintype "bidirectional"))
      (node (ref "TP47") (pin "TP") (pinfunction "TP_TP") (pintype "input"))
    )
    (net (code "86") (name "Net-(IC3-UCAP)") (class "Default")
      (node (ref "IC3") (pin "27") (pinfunction "UCAP_27") (pintype "bidirectional"))
      (node (ref "TP6") (pin "TP") (pinfunction "TP_TP") (pintype "input"))
    )
    (net (code "87") (name "Net-(IC3-UGND)") (class "Default")
      (node (ref "IC3") (pin "28") (pinfunction "UGND_28") (pintype "bidirectional"))
      (node (ref "TP38") (pin "TP") (pinfunction "TP_TP") (pintype "input"))
    )
    (net (code "88") (name "Net-(IC3-UVCC)") (class "Default")
      (node (ref "IC3") (pin "31") (pinfunction "UVCC_31") (pintype "bidirectional"))
      (node (ref "TP2") (pin "TP") (pinfunction "TP_TP") (pintype "input"))
    )
    (net (code "89") (name "Net-(IC3-VCC)") (class "Default")
      (node (ref "IC3") (pin "4") (pinfunction "VCC_4") (pintype "bidirectional"))
      (node (ref "TP1") (pin "TP") (pinfunction "TP_TP") (pintype "input"))
    )
    (net (code "90") (name "Net-(IC3-XTAL1)") (class "Default")
      (node (ref "IC3") (pin "1") (pinfunction "XTAL1_1") (pintype "bidirectional"))
      (node (ref "TP7") (pin "TP") (pinfunction "TP_TP") (pintype "input"))
    )
    (net (code "91") (name "Net-(IC3-XTAL2{slash}PC0)") (class "Default")
      (node (ref "IC3") (pin "2") (pinfunction "XTAL2/PC0_2") (pintype "bidirectional"))
      (node (ref "TP8") (pin "TP") (pinfunction "TP_TP") (pintype "input"))
    )
    (net (code "92") (name "Net-(IC3-{slash}RESET(PC1))") (class "Default")
      (node (ref "IC3") (pin "24") (pinfunction "/RESET(PC1)_24") (pintype "bidirectional"))
      (node (ref "TP37") (pin "TP") (pinfunction "TP_TP") (pintype "input"))
    )
  )
)
